# Indicator.net
KiCad netlist of a schematic drawn in Altium Designer
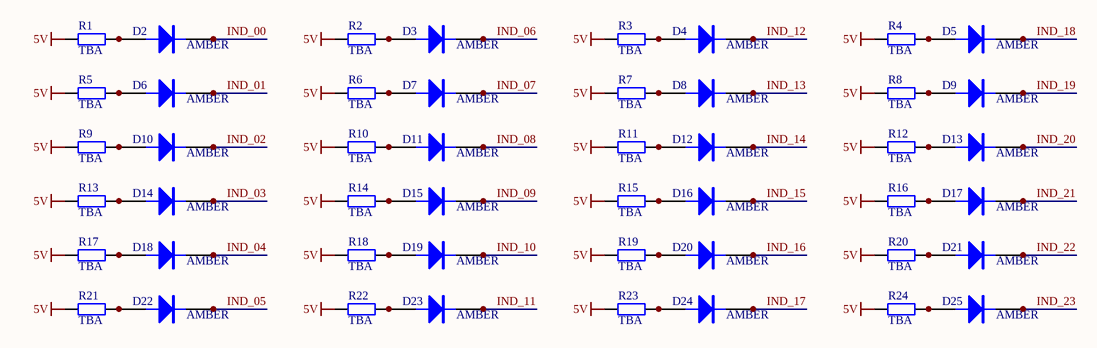
[diagram p0: Indicator.SchDoc]

(export (version "E")
  (design (tool "Eeschema 10.0.6"))
  (components
    (comp (ref "D2")
      (value "AMBER")
      (footprint "CREE P4 YELLOW")
      (description "CREE AMBER LED P4 (SUPERFLUX)")
      (libsource (lib "LED TAIL LIGHTS") (part "CP41B-AFSCM0Q0264"))
    )
    (comp (ref "D3")
      (value "AMBER")
      (footprint "CREE P4 YELLOW")
      (description "CREE AMBER LED P4 (SUPERFLUX)")
      (libsource (lib "LED TAIL LIGHTS") (part "CP41B-AFSCM0Q0264"))
    )
    (comp (ref "D4")
      (value "AMBER")
      (footprint "CREE P4 YELLOW")
      (description "CREE AMBER LED P4 (SUPERFLUX)")
      (libsource (lib "LED TAIL LIGHTS") (part "CP41B-AFSCM0Q0264"))
    )
    (comp (ref "D5")
      (value "AMBER")
      (footprint "CREE P4 YELLOW")
      (description "CREE AMBER LED P4 (SUPERFLUX)")
      (libsource (lib "LED TAIL LIGHTS") (part "CP41B-AFSCM0Q0264"))
    )
    (comp (ref "D6")
      (value "AMBER")
      (footprint "CREE P4 YELLOW")
      (description "CREE AMBER LED P4 (SUPERFLUX)")
      (libsource (lib "LED TAIL LIGHTS") (part "CP41B-AFSCM0Q0264"))
    )
    (comp (ref "D7")
      (value "AMBER")
      (footprint "CREE P4 YELLOW")
      (description "CREE AMBER LED P4 (SUPERFLUX)")
      (libsource (lib "LED TAIL LIGHTS") (part "CP41B-AFSCM0Q0264"))
    )
    (comp (ref "D8")
      (value "AMBER")
      (footprint "CREE P4 YELLOW")
      (description "CREE AMBER LED P4 (SUPERFLUX)")
      (libsource (lib "LED TAIL LIGHTS") (part "CP41B-AFSCM0Q0264"))
    )
    (comp (ref "D9")
      (value "AMBER")
      (footprint "CREE P4 YELLOW")
      (description "CREE AMBER LED P4 (SUPERFLUX)")
      (libsource (lib "LED TAIL LIGHTS") (part "CP41B-AFSCM0Q0264"))
    )
    (comp (ref "D10")
      (value "AMBER")
      (footprint "CREE P4 YELLOW")
      (description "CREE AMBER LED P4 (SUPERFLUX)")
      (libsource (lib "LED TAIL LIGHTS") (part "CP41B-AFSCM0Q0264"))
    )
    (comp (ref "D11")
      (value "AMBER")
      (footprint "CREE P4 YELLOW")
      (description "CREE AMBER LED P4 (SUPERFLUX)")
      (libsource (lib "LED TAIL LIGHTS") (part "CP41B-AFSCM0Q0264"))
    )
    (comp (ref "D12")
      (value "AMBER")
      (footprint "CREE P4 YELLOW")
      (description "CREE AMBER LED P4 (SUPERFLUX)")
      (libsource (lib "LED TAIL LIGHTS") (part "CP41B-AFSCM0Q0264"))
    )
    (comp (ref "D13")
      (value "AMBER")
      (footprint "CREE P4 YELLOW")
      (description "CREE AMBER LED P4 (SUPERFLUX)")
      (libsource (lib "LED TAIL LIGHTS") (part "CP41B-AFSCM0Q0264"))
    )
    (comp (ref "D14")
      (value "AMBER")
      (footprint "CREE P4 YELLOW")
      (description "CREE AMBER LED P4 (SUPERFLUX)")
      (libsource (lib "LED TAIL LIGHTS") (part "CP41B-AFSCM0Q0264"))
    )
    (comp (ref "D15")
      (value "AMBER")
      (footprint "CREE P4 YELLOW")
      (description "CREE AMBER LED P4 (SUPERFLUX)")
      (libsource (lib "LED TAIL LIGHTS") (part "CP41B-AFSCM0Q0264"))
    )
    (comp (ref "D16")
      (value "AMBER")
      (footprint "CREE P4 YELLOW")
      (description "CREE AMBER LED P4 (SUPERFLUX)")
      (libsource (lib "LED TAIL LIGHTS") (part "CP41B-AFSCM0Q0264"))
    )
    (comp (ref "D17")
      (value "AMBER")
      (footprint "CREE P4 YELLOW")
      (description "CREE AMBER LED P4 (SUPERFLUX)")
      (libsource (lib "LED TAIL LIGHTS") (part "CP41B-AFSCM0Q0264"))
    )
    (comp (ref "D18")
      (value "AMBER")
      (footprint "CREE P4 YELLOW")
      (description "CREE AMBER LED P4 (SUPERFLUX)")
      (libsource (lib "LED TAIL LIGHTS") (part "CP41B-AFSCM0Q0264"))
    )
    (comp (ref "D19")
      (value "AMBER")
      (footprint "CREE P4 YELLOW")
      (description "CREE AMBER LED P4 (SUPERFLUX)")
      (libsource (lib "LED TAIL LIGHTS") (part "CP41B-AFSCM0Q0264"))
    )
    (comp (ref "D20")
      (value "AMBER")
      (footprint "CREE P4 YELLOW")
      (description "CREE AMBER LED P4 (SUPERFLUX)")
      (libsource (lib "LED TAIL LIGHTS") (part "CP41B-AFSCM0Q0264"))
    )
    (comp (ref "D21")
      (value "AMBER")
      (footprint "CREE P4 YELLOW")
      (description "CREE AMBER LED P4 (SUPERFLUX)")
      (libsource (lib "LED TAIL LIGHTS") (part "CP41B-AFSCM0Q0264"))
    )
    (comp (ref "D22")
      (value "AMBER")
      (footprint "CREE P4 YELLOW")
      (description "CREE AMBER LED P4 (SUPERFLUX)")
      (libsource (lib "LED TAIL LIGHTS") (part "CP41B-AFSCM0Q0264"))
    )
    (comp (ref "D23")
      (value "AMBER")
      (footprint "CREE P4 YELLOW")
      (description "CREE AMBER LED P4 (SUPERFLUX)")
      (libsource (lib "LED TAIL LIGHTS") (part "CP41B-AFSCM0Q0264"))
    )
    (comp (ref "D24")
      (value "AMBER")
      (footprint "CREE P4 YELLOW")
      (description "CREE AMBER LED P4 (SUPERFLUX)")
      (libsource (lib "LED TAIL LIGHTS") (part "CP41B-AFSCM0Q0264"))
    )
    (comp (ref "D25")
      (value "AMBER")
      (footprint "CREE P4 YELLOW")
      (description "CREE AMBER LED P4 (SUPERFLUX)")
      (libsource (lib "LED TAIL LIGHTS") (part "CP41B-AFSCM0Q0264"))
    )
    (comp (ref "R1")
      (value "TBA")
      (footprint "newpcb:RESISTOR 0.400\"")
      (description "RESISITOR THROUGH HOLE 1/4W")
      (libsource (lib "FavoritesLibrary") (part "SYM-iaxfckaaxq3jb0c9euu5-1"))
    )
    (comp (ref "R2")
      (value "TBA")
      (footprint "newpcb:RESISTOR 0.400\"")
      (description "RESISITOR THROUGH HOLE 1/4W")
      (libsource (lib "FavoritesLibrary") (part "SYM-iaxfckaaxq3jb0c9euu5-1"))
    )
    (comp (ref "R3")
      (value "TBA")
      (footprint "newpcb:RESISTOR 0.400\"")
      (description "RESISITOR THROUGH HOLE 1/4W")
      (libsource (lib "FavoritesLibrary") (part "SYM-iaxfckaaxq3jb0c9euu5-1"))
    )
    (comp (ref "R4")
      (value "TBA")
      (footprint "newpcb:RESISTOR 0.400\"")
      (description "RESISITOR THROUGH HOLE 1/4W")
      (libsource (lib "FavoritesLibrary") (part "SYM-iaxfckaaxq3jb0c9euu5-1"))
    )
    (comp (ref "R5")
      (value "TBA")
      (footprint "newpcb:RESISTOR 0.400\"")
      (description "RESISITOR THROUGH HOLE 1/4W")
      (libsource (lib "FavoritesLibrary") (part "SYM-iaxfckaaxq3jb0c9euu5-1"))
    )
    (comp (ref "R6")
      (value "TBA")
      (footprint "newpcb:RESISTOR 0.400\"")
      (description "RESISITOR THROUGH HOLE 1/4W")
      (libsource (lib "FavoritesLibrary") (part "SYM-iaxfckaaxq3jb0c9euu5-1"))
    )
    (comp (ref "R7")
      (value "TBA")
      (footprint "newpcb:RESISTOR 0.400\"")
      (description "RESISITOR THROUGH HOLE 1/4W")
      (libsource (lib "FavoritesLibrary") (part "SYM-iaxfckaaxq3jb0c9euu5-1"))
    )
    (comp (ref "R8")
      (value "TBA")
      (footprint "newpcb:RESISTOR 0.400\"")
      (description "RESISITOR THROUGH HOLE 1/4W")
      (libsource (lib "FavoritesLibrary") (part "SYM-iaxfckaaxq3jb0c9euu5-1"))
    )
    (comp (ref "R9")
      (value "TBA")
      (footprint "newpcb:RESISTOR 0.400\"")
      (description "RESISITOR THROUGH HOLE 1/4W")
      (libsource (lib "FavoritesLibrary") (part "SYM-iaxfckaaxq3jb0c9euu5-1"))
    )
    (comp (ref "R10")
      (value "TBA")
      (footprint "newpcb:RESISTOR 0.400\"")
      (description "RESISITOR THROUGH HOLE 1/4W")
      (libsource (lib "FavoritesLibrary") (part "SYM-iaxfckaaxq3jb0c9euu5-1"))
    )
    (comp (ref "R11")
      (value "TBA")
      (footprint "newpcb:RESISTOR 0.400\"")
      (description "RESISITOR THROUGH HOLE 1/4W")
      (libsource (lib "FavoritesLibrary") (part "SYM-iaxfckaaxq3jb0c9euu5-1"))
    )
    (comp (ref "R12")
      (value "TBA")
      (footprint "newpcb:RESISTOR 0.400\"")
      (description "RESISITOR THROUGH HOLE 1/4W")
      (libsource (lib "FavoritesLibrary") (part "SYM-iaxfckaaxq3jb0c9euu5-1"))
    )
    (comp (ref "R13")
      (value "TBA")
      (footprint "newpcb:RESISTOR 0.400\"")
      (description "RESISITOR THROUGH HOLE 1/4W")
      (libsource (lib "FavoritesLibrary") (part "SYM-iaxfckaaxq3jb0c9euu5-1"))
    )
    (comp (ref "R14")
      (value "TBA")
      (footprint "newpcb:RESISTOR 0.400\"")
      (description "RESISITOR THROUGH HOLE 1/4W")
      (libsource (lib "FavoritesLibrary") (part "SYM-iaxfckaaxq3jb0c9euu5-1"))
    )
    (comp (ref "R15")
      (value "TBA")
      (footprint "newpcb:RESISTOR 0.400\"")
      (description "RESISITOR THROUGH HOLE 1/4W")
      (libsource (lib "FavoritesLibrary") (part "SYM-iaxfckaaxq3jb0c9euu5-1"))
    )
    (comp (ref "R16")
      (value "TBA")
      (footprint "newpcb:RESISTOR 0.400\"")
      (description "RESISITOR THROUGH HOLE 1/4W")
      (libsource (lib "FavoritesLibrary") (part "SYM-iaxfckaaxq3jb0c9euu5-1"))
    )
    (comp (ref "R17")
      (value "TBA")
      (footprint "newpcb:RESISTOR 0.400\"")
      (description "RESISITOR THROUGH HOLE 1/4W")
      (libsource (lib "FavoritesLibrary") (part "SYM-iaxfckaaxq3jb0c9euu5-1"))
    )
    (comp (ref "R18")
      (value "TBA")
      (footprint "newpcb:RESISTOR 0.400\"")
      (description "RESISITOR THROUGH HOLE 1/4W")
      (libsource (lib "FavoritesLibrary") (part "SYM-iaxfckaaxq3jb0c9euu5-1"))
    )
    (comp (ref "R19")
      (value "TBA")
      (footprint "newpcb:RESISTOR 0.400\"")
      (description "RESISITOR THROUGH HOLE 1/4W")
      (libsource (lib "FavoritesLibrary") (part "SYM-iaxfckaaxq3jb0c9euu5-1"))
    )
    (comp (ref "R20")
      (value "TBA")
      (footprint "newpcb:RESISTOR 0.400\"")
      (description "RESISITOR THROUGH HOLE 1/4W")
      (libsource (lib "FavoritesLibrary") (part "SYM-iaxfckaaxq3jb0c9euu5-1"))
    )
    (comp (ref "R21")
      (value "TBA")
      (footprint "newpcb:RESISTOR 0.400\"")
      (description "RESISITOR THROUGH HOLE 1/4W")
      (libsource (lib "FavoritesLibrary") (part "SYM-iaxfckaaxq3jb0c9euu5-1"))
    )
    (comp (ref "R22")
      (value "TBA")
      (footprint "newpcb:RESISTOR 0.400\"")
      (description "RESISITOR THROUGH HOLE 1/4W")
      (libsource (lib "FavoritesLibrary") (part "SYM-iaxfckaaxq3jb0c9euu5-1"))
    )
    (comp (ref "R23")
      (value "TBA")
      (footprint "newpcb:RESISTOR 0.400\"")
      (description "RESISITOR THROUGH HOLE 1/4W")
      (libsource (lib "FavoritesLibrary") (part "SYM-iaxfckaaxq3jb0c9euu5-1"))
    )
    (comp (ref "R24")
      (value "TBA")
      (footprint "newpcb:RESISTOR 0.400\"")
      (description "RESISITOR THROUGH HOLE 1/4W")
      (libsource (lib "FavoritesLibrary") (part "SYM-iaxfckaaxq3jb0c9euu5-1"))
    )
  )
  (nets
    (net (code "1") (name "/IND_00") (class "Default")
      (node (ref "D2") (pin "1") (pinfunction "K_1") (pintype "passive"))
      (node (ref "D2") (pin "4") (pinfunction "K_4") (pintype "passive"))
    )
    (net (code "2") (name "/IND_01") (class "Default")
      (node (ref "D6") (pin "1") (pinfunction "K_1") (pintype "passive"))
      (node (ref "D6") (pin "4") (pinfunction "K_4") (pintype "passive"))
    )
    (net (code "3") (name "/IND_02") (class "Default")
      (node (ref "D10") (pin "1") (pinfunction "K_1") (pintype "passive"))
      (node (ref "D10") (pin "4") (pinfunction "K_4") (pintype "passive"))
    )
    (net (code "4") (name "/IND_03") (class "Default")
      (node (ref "D14") (pin "1") (pinfunction "K_1") (pintype "passive"))
      (node (ref "D14") (pin "4") (pinfunction "K_4") (pintype "passive"))
    )
    (net (code "5") (name "/IND_04") (class "Default")
      (node (ref "D18") (pin "1") (pinfunction "K_1") (pintype "passive"))
      (node (ref "D18") (pin "4") (pinfunction "K_4") (pintype "passive"))
    )
    (net (code "6") (name "/IND_05") (class "Default")
      (node (ref "D22") (pin "1") (pinfunction "K_1") (pintype "passive"))
      (node (ref "D22") (pin "4") (pinfunction "K_4") (pintype "passive"))
    )
    (net (code "7") (name "/IND_06") (class "Default")
      (node (ref "D3") (pin "1") (pinfunction "K_1") (pintype "passive"))
      (node (ref "D3") (pin "4") (pinfunction "K_4") (pintype "passive"))
    )
    (net (code "8") (name "/IND_07") (class "Default")
      (node (ref "D7") (pin "1") (pinfunction "K_1") (pintype "passive"))
      (node (ref "D7") (pin "4") (pinfunction "K_4") (pintype "passive"))
    )
    (net (code "9") (name "/IND_08") (class "Default")
      (node (ref "D11") (pin "1") (pinfunction "K_1") (pintype "passive"))
      (node (ref "D11") (pin "4") (pinfunction "K_4") (pintype "passive"))
    )
    (net (code "10") (name "/IND_09") (class "Default")
      (node (ref "D15") (pin "1") (pinfunction "K_1") (pintype "passive"))
      (node (ref "D15") (pin "4") (pinfunction "K_4") (pintype "passive"))
    )
    (net (code "11") (name "/IND_10") (class "Default")
      (node (ref "D19") (pin "1") (pinfunction "K_1") (pintype "passive"))
      (node (ref "D19") (pin "4") (pinfunction "K_4") (pintype "passive"))
    )
    (net (code "12") (name "/IND_11") (class "Default")
      (node (ref "D23") (pin "1") (pinfunction "K_1") (pintype "passive"))
      (node (ref "D23") (pin "4") (pinfunction "K_4") (pintype "passive"))
    )
    (net (code "13") (name "/IND_12") (class "Default")
      (node (ref "D4") (pin "1") (pinfunction "K_1") (pintype "passive"))
      (node (ref "D4") (pin "4") (pinfunction "K_4") (pintype "passive"))
    )
    (net (code "14") (name "/IND_13") (class "Default")
      (node (ref "D8") (pin "1") (pinfunction "K_1") (pintype "passive"))
      (node (ref "D8") (pin "4") (pinfunction "K_4") (pintype "passive"))
    )
    (net (code "15") (name "/IND_14") (class "Default")
      (node (ref "D12") (pin "1") (pinfunction "K_1") (pintype "passive"))
      (node (ref "D12") (pin "4") (pinfunction "K_4") (pintype "passive"))
    )
    (net (code "16") (name "/IND_15") (class "Default")
      (node (ref "D16") (pin "1") (pinfunction "K_1") (pintype "passive"))
      (node (ref "D16") (pin "4") (pinfunction "K_4") (pintype "passive"))
    )
    (net (code "17") (name "/IND_16") (class "Default")
      (node (ref "D20") (pin "1") (pinfunction "K_1") (pintype "passive"))
      (node (ref "D20") (pin "4") (pinfunction "K_4") (pintype "passive"))
    )
    (net (code "18") (name "/IND_17") (class "Default")
      (node (ref "D24") (pin "1") (pinfunction "K_1") (pintype "passive"))
      (node (ref "D24") (pin "4") (pinfunction "K_4") (pintype "passive"))
    )
    (net (code "19") (name "/IND_18") (class "Default")
      (node (ref "D5") (pin "1") (pinfunction "K_1") (pintype "passive"))
      (node (ref "D5") (pin "4") (pinfunction "K_4") (pintype "passive"))
    )
    (net (code "20") (name "/IND_19") (class "Default")
      (node (ref "D9") (pin "1") (pinfunction "K_1") (pintype "passive"))
      (node (ref "D9") (pin "4") (pinfunction "K_4") (pintype "passive"))
    )
    (net (code "21") (name "/IND_20") (class "Default")
      (node (ref "D13") (pin "1") (pinfunction "K_1") (pintype "passive"))
      (node (ref "D13") (pin "4") (pinfunction "K_4") (pintype "passive"))
    )
    (net (code "22") (name "/IND_21") (class "Default")
      (node (ref "D17") (pin "1") (pinfunction "K_1") (pintype "passive"))
      (node (ref "D17") (pin "4") (pinfunction "K_4") (pintype "passive"))
    )
    (net (code "23") (name "/IND_22") (class "Default")
      (node (ref "D21") (pin "1") (pinfunction "K_1") (pintype "passive"))
      (node (ref "D21") (pin "4") (pinfunction "K_4") (pintype "passive"))
    )
    (net (code "24") (name "/IND_23") (class "Default")
      (node (ref "D25") (pin "1") (pinfunction "K_1") (pintype "passive"))
      (node (ref "D25") (pin "4") (pinfunction "K_4") (pintype "passive"))
    )
    (net (code "25") (name "5V") (class "Default")
      (node (ref "R1") (pin "2") (pinfunction "2_2") (pintype "passive"))
      (node (ref "R10") (pin "2") (pinfunction "2_2") (pintype "passive"))
      (node (ref "R11") (pin "2") (pinfunction "2_2") (pintype "passive"))
      (node (ref "R12") (pin "2") (pinfunction "2_2") (pintype "passive"))
      (node (ref "R13") (pin "2") (pinfunction "2_2") (pintype "passive"))
      (node (ref "R14") (pin "2") (pinfunction "2_2") (pintype "passive"))
      (node (ref "R15") (pin "2") (pinfunction "2_2") (pintype "passive"))
      (node (ref "R16") (pin "2") (pinfunction "2_2") (pintype "passive"))
      (node (ref "R17") (pin "2") (pinfunction "2_2") (pintype "passive"))
      (node (ref "R18") (pin "2") (pinfunction "2_2") (pintype "passive"))
      (node (ref "R19") (pin "2") (pinfunction "2_2") (pintype "passive"))
      (node (ref "R2") (pin "2") (pinfunction "2_2") (pintype "passive"))
      (node (ref "R20") (pin "2") (pinfunction "2_2") (pintype "passive"))
      (node (ref "R21") (pin "2") (pinfunction "2_2") (pintype "passive"))
      (node (ref "R22") (pin "2") (pinfunction "2_2") (pintype "passive"))
      (node (ref "R23") (pin "2") (pinfunction "2_2") (pintype "passive"))
      (node (ref "R24") (pin "2") (pinfunction "2_2") (pintype "passive"))
      (node (ref "R3") (pin "2") (pinfunction "2_2") (pintype "passive"))
      (node (ref "R4") (pin "2") (pinfunction "2_2") (pintype "passive"))
      (node (ref "R5") (pin "2") (pinfunction "2_2") (pintype "passive"))
      (node (ref "R6") (pin "2") (pinfunction "2_2") (pintype "passive"))
      (node (ref "R7") (pin "2") (pinfunction "2_2") (pintype "passive"))
      (node (ref "R8") (pin "2") (pinfunction "2_2") (pintype "passive"))
      (node (ref "R9") (pin "2") (pinfunction "2_2") (pintype "passive"))
    )
    (net (code "26") (name "Net-(D2-A-Pad2)") (class "Default")
      (node (ref "D2") (pin "2") (pinfunction "A_2") (pintype "passive"))
      (node (ref "D2") (pin "3") (pinfunction "A_3") (pintype "passive"))
      (node (ref "R1") (pin "1") (pinfunction "1_1") (pintype "passive"))
    )
    (net (code "27") (name "Net-(D3-A-Pad2)") (class "Default")
      (node (ref "D3") (pin "2") (pinfunction "A_2") (pintype "passive"))
      (node (ref "D3") (pin "3") (pinfunction "A_3") (pintype "passive"))
      (node (ref "R2") (pin "1") (pinfunction "1_1") (pintype "passive"))
    )
    (net (code "28") (name "Net-(D4-A-Pad2)") (class "Default")
      (node (ref "D4") (pin "2") (pinfunction "A_2") (pintype "passive"))
      (node (ref "D4") (pin "3") (pinfunction "A_3") (pintype "passive"))
      (node (ref "R3") (pin "1") (pinfunction "1_1") (pintype "passive"))
    )
    (net (code "29") (name "Net-(D5-A-Pad2)") (class "Default")
      (node (ref "D5") (pin "2") (pinfunction "A_2") (pintype "passive"))
      (node (ref "D5") (pin "3") (pinfunction "A_3") (pintype "passive"))
      (node (ref "R4") (pin "1") (pinfunction "1_1") (pintype "passive"))
    )
    (net (code "30") (name "Net-(D6-A-Pad2)") (class "Default")
      (node (ref "D6") (pin "2") (pinfunction "A_2") (pintype "passive"))
      (node (ref "D6") (pin "3") (pinfunction "A_3") (pintype "passive"))
      (node (ref "R5") (pin "1") (pinfunction "1_1") (pintype "passive"))
    )
    (net (code "31") (name "Net-(D7-A-Pad2)") (class "Default")
      (node (ref "D7") (pin "2") (pinfunction "A_2") (pintype "passive"))
      (node (ref "D7") (pin "3") (pinfunction "A_3") (pintype "passive"))
      (node (ref "R6") (pin "1") (pinfunction "1_1") (pintype "passive"))
    )
    (net (code "32") (name "Net-(D8-A-Pad2)") (class "Default")
      (node (ref "D8") (pin "2") (pinfunction "A_2") (pintype "passive"))
      (node (ref "D8") (pin "3") (pinfunction "A_3") (pintype "passive"))
      (node (ref "R7") (pin "1") (pinfunction "1_1") (pintype "passive"))
    )
    (net (code "33") (name "Net-(D9-A-Pad2)") (class "Default")
      (node (ref "D9") (pin "2") (pinfunction "A_2") (pintype "passive"))
      (node (ref "D9") (pin "3") (pinfunction "A_3") (pintype "passive"))
      (node (ref "R8") (pin "1") (pinfunction "1_1") (pintype "passive"))
    )
    (net (code "34") (name "Net-(D10-A-Pad2)") (class "Default")
      (node (ref "D10") (pin "2") (pinfunction "A_2") (pintype "passive"))
      (node (ref "D10") (pin "3") (pinfunction "A_3") (pintype "passive"))
      (node (ref "R9") (pin "1") (pinfunction "1_1") (pintype "passive"))
    )
    (net (code "35") (name "Net-(D11-A-Pad2)") (class "Default")
      (node (ref "D11") (pin "2") (pinfunction "A_2") (pintype "passive"))
      (node (ref "D11") (pin "3") (pinfunction "A_3") (pintype "passive"))
      (node (ref "R10") (pin "1") (pinfunction "1_1") (pintype "passive"))
    )
    (net (code "36") (name "Net-(D12-A-Pad2)") (class "Default")
      (node (ref "D12") (pin "2") (pinfunction "A_2") (pintype "passive"))
      (node (ref "D12") (pin "3") (pinfunction "A_3") (pintype "passive"))
      (node (ref "R11") (pin "1") (pinfunction "1_1") (pintype "passive"))
    )
    (net (code "37") (name "Net-(D13-A-Pad2)") (class "Default")
      (node (ref "D13") (pin "2") (pinfunction "A_2") (pintype "passive"))
      (node (ref "D13") (pin "3") (pinfunction "A_3") (pintype "passive"))
      (node (ref "R12") (pin "1") (pinfunction "1_1") (pintype "passive"))
    )
    (net (code "38") (name "Net-(D14-A-Pad2)") (class "Default")
      (node (ref "D14") (pin "2") (pinfunction "A_2") (pintype "passive"))
      (node (ref "D14") (pin "3") (pinfunction "A_3") (pintype "passive"))
      (node (ref "R13") (pin "1") (pinfunction "1_1") (pintype "passive"))
    )
    (net (code "39") (name "Net-(D15-A-Pad2)") (class "Default")
      (node (ref "D15") (pin "2") (pinfunction "A_2") (pintype "passive"))
      (node (ref "D15") (pin "3") (pinfunction "A_3") (pintype "passive"))
      (node (ref "R14") (pin "1") (pinfunction "1_1") (pintype "passive"))
    )
    (net (code "40") (name "Net-(D16-A-Pad2)") (class "Default")
      (node (ref "D16") (pin "2") (pinfunction "A_2") (pintype "passive"))
      (node (ref "D16") (pin "3") (pinfunction "A_3") (pintype "passive"))
      (node (ref "R15") (pin "1") (pinfunction "1_1") (pintype "passive"))
    )
    (net (code "41") (name "Net-(D17-A-Pad2)") (class "Default")
      (node (ref "D17") (pin "2") (pinfunction "A_2") (pintype "passive"))
      (node (ref "D17") (pin "3") (pinfunction "A_3") (pintype "passive"))
      (node (ref "R16") (pin "1") (pinfunction "1_1") (pintype "passive"))
    )
    (net (code "42") (name "Net-(D18-A-Pad2)") (class "Default")
      (node (ref "D18") (pin "2") (pinfunction "A_2") (pintype "passive"))
      (node (ref "D18") (pin "3") (pinfunction "A_3") (pintype "passive"))
      (node (ref "R17") (pin "1") (pinfunction "1_1") (pintype "passive"))
    )
    (net (code "43") (name "Net-(D19-A-Pad2)") (class "Default")
      (node (ref "D19") (pin "2") (pinfunction "A_2") (pintype "passive"))
      (node (ref "D19") (pin "3") (pinfunction "A_3") (pintype "passive"))
      (node (ref "R18") (pin "1") (pinfunction "1_1") (pintype "passive"))
    )
    (net (code "44") (name "Net-(D20-A-Pad2)") (class "Default")
      (node (ref "D20") (pin "2") (pinfunction "A_2") (pintype "passive"))
      (node (ref "D20") (pin "3") (pinfunction "A_3") (pintype "passive"))
      (node (ref "R19") (pin "1") (pinfunction "1_1") (pintype "passive"))
    )
    (net (code "45") (name "Net-(D21-A-Pad2)") (class "Default")
      (node (ref "D21") (pin "2") (pinfunction "A_2") (pintype "passive"))
      (node (ref "D21") (pin "3") (pinfunction "A_3") (pintype "passive"))
      (node (ref "R20") (pin "1") (pinfunction "1_1") (pintype "passive"))
    )
    (net (code "46") (name "Net-(D22-A-Pad2)") (class "Default")
      (node (ref "D22") (pin "2") (pinfunction "A_2") (pintype "passive"))
      (node (ref "D22") (pin "3") (pinfunction "A_3") (pintype "passive"))
      (node (ref "R21") (pin "1") (pinfunction "1_1") (pintype "passive"))
    )
    (net (code "47") (name "Net-(D23-A-Pad2)") (class "Default")
      (node (ref "D23") (pin "2") (pinfunction "A_2") (pintype "passive"))
      (node (ref "D23") (pin "3") (pinfunction "A_3") (pintype "passive"))
      (node (ref "R22") (pin "1") (pinfunction "1_1") (pintype "passive"))
    )
    (net (code "48") (name "Net-(D24-A-Pad2)") (class "Default")
      (node (ref "D24") (pin "2") (pinfunction "A_2") (pintype "passive"))
      (node (ref "D24") (pin "3") (pinfunction "A_3") (pintype "passive"))
      (node (ref "R23") (pin "1") (pinfunction "1_1") (pintype "passive"))
    )
    (net (code "49") (name "Net-(D25-A-Pad2)") (class "Default")
      (node (ref "D25") (pin "2") (pinfunction "A_2") (pintype "passive"))
      (node (ref "D25") (pin "3") (pinfunction "A_3") (pintype "passive"))
      (node (ref "R24") (pin "1") (pinfunction "1_1") (pintype "passive"))
    )
  )
)
